# Adafruit_SHT31-D_STEMMA_QT_Breakout.net
KiCad netlist of a schematic drawn in EAGLE
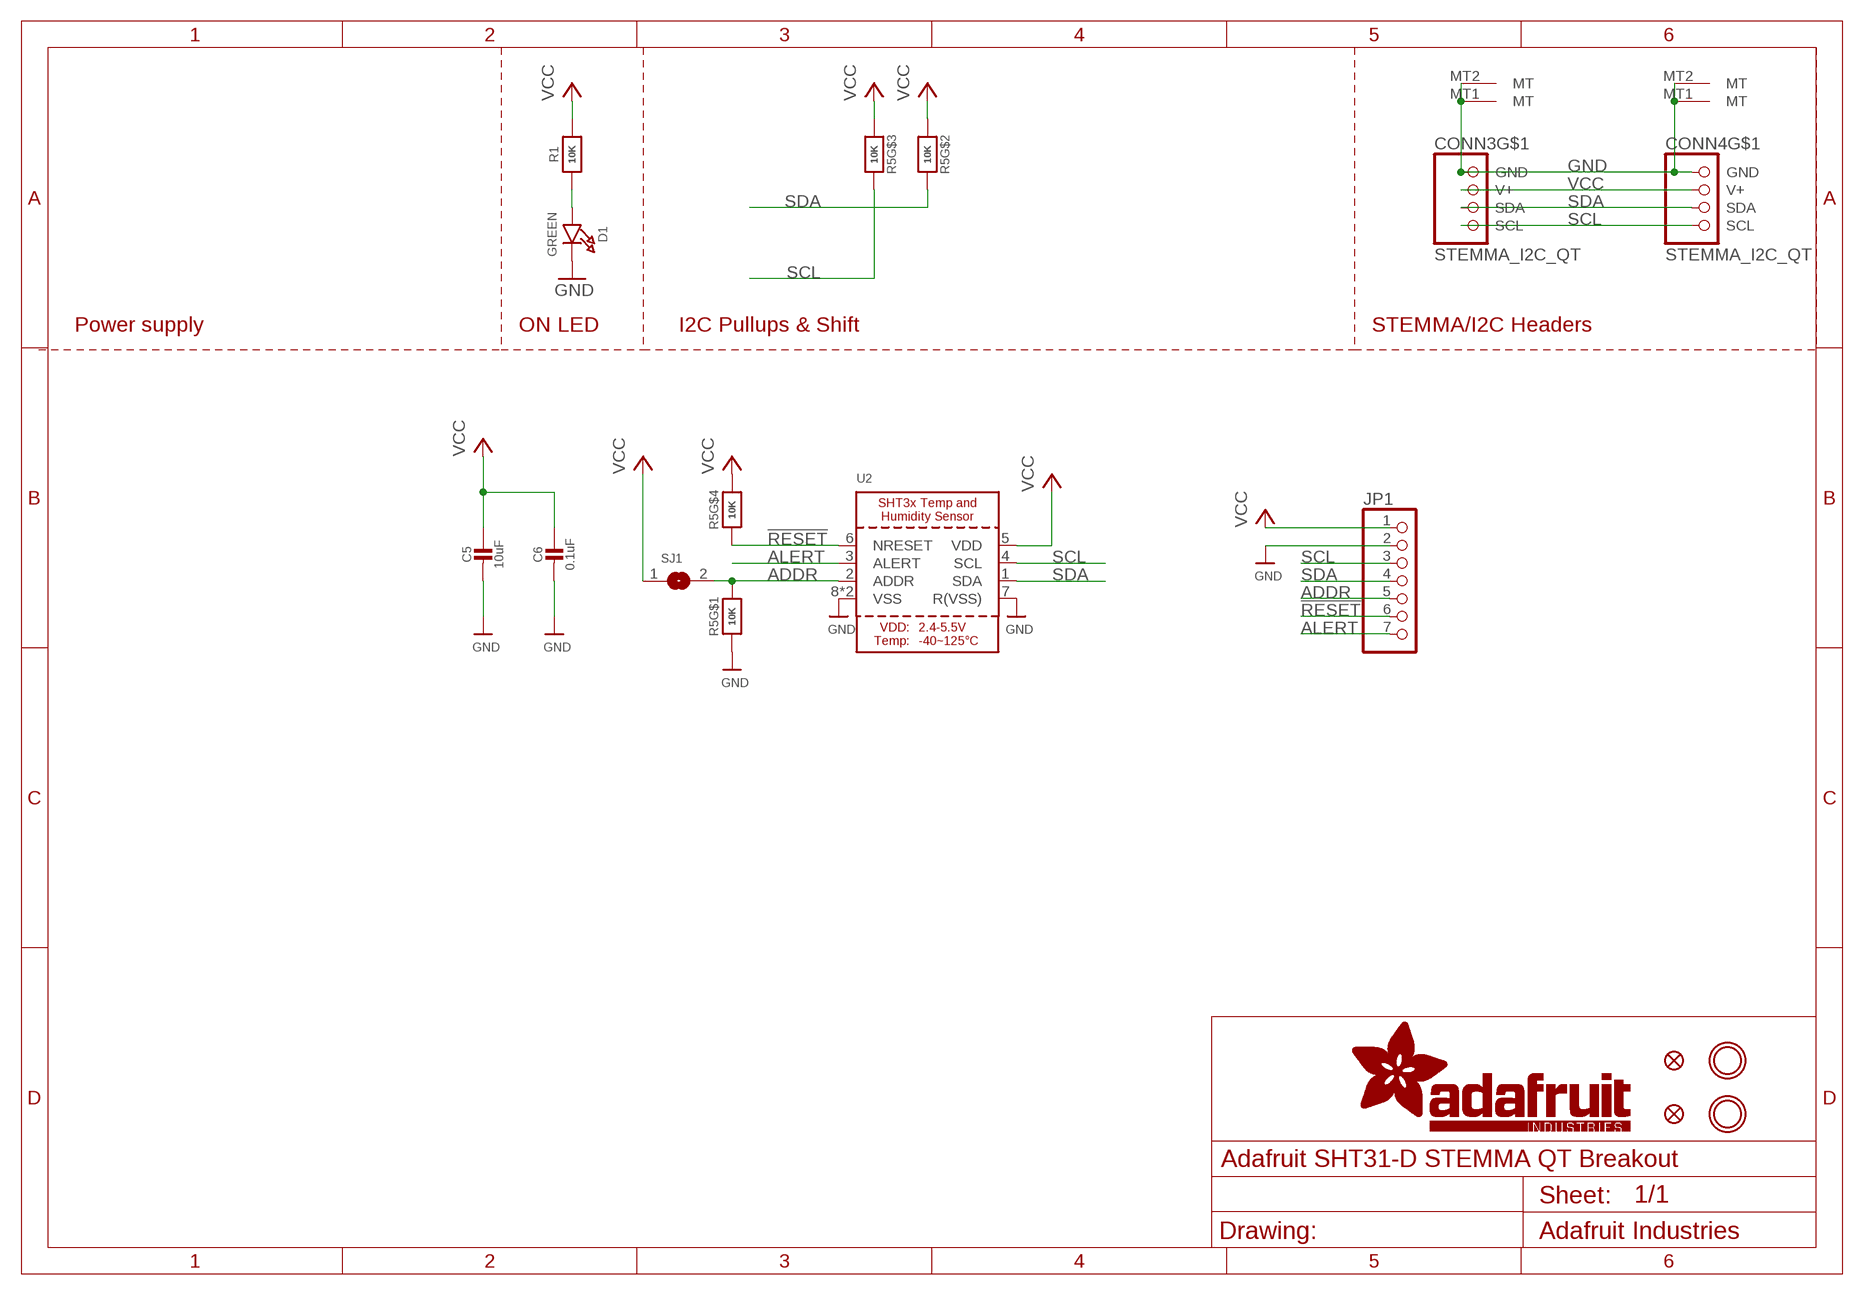
[diagram p0: schematic, sheet 1]

(export (version "E")
  (design (tool "Eeschema 10.0.6"))
  (components
    (comp (ref "C5")
      (value "10uF")
      (footprint "eagle-import:0805-NO")
      (libsource (lib "eagle-import") (part "CAP_CERAMIC0805-NOOUTLINE"))
    )
    (comp (ref "C6")
      (value "0.1uF")
      (footprint "eagle-import:0603-NO")
      (libsource (lib "eagle-import") (part "CAP_CERAMIC0603_NO"))
    )
    (comp (ref "CONN3")
      (value "STEMMA_I2C_QT")
      (footprint "eagle-import:JST_SH4")
      (libsource (lib "eagle-import") (part "STEMMA_I2C_QT"))
    )
    (comp (ref "CONN4")
      (value "STEMMA_I2C_QT")
      (footprint "eagle-import:JST_SH4")
      (libsource (lib "eagle-import") (part "STEMMA_I2C_QT"))
    )
    (comp (ref "D1")
      (value "GREEN")
      (footprint "eagle-import:CHIPLED_0603_NOOUTLINE")
      (libsource (lib "eagle-import") (part "LED0603_NOOUTLINE"))
    )
    (comp (ref "FID3")
      (value "FIDUCIAL_1MM")
      (footprint "eagle-import:FIDUCIAL_1MM")
      (libsource (lib "eagle-import") (part "FIDUCIAL_1MM"))
    )
    (comp (ref "FID4")
      (value "FIDUCIAL_1MM")
      (footprint "eagle-import:FIDUCIAL_1MM")
      (libsource (lib "eagle-import") (part "FIDUCIAL_1MM"))
    )
    (comp (ref "JP1")
      (value "HEADER-1X770MIL")
      (footprint "eagle-import:1X07_ROUND_70")
      (libsource (lib "eagle-import") (part "HEADER-1X770MIL"))
    )
    (comp (ref "R1")
      (value "10K")
      (footprint "eagle-import:0603-NO")
      (libsource (lib "eagle-import") (part "RESISTOR_0603_NOOUT"))
    )
    (comp (ref "R5")
      (value "10K")
      (footprint "eagle-import:RESPACK_4X0603")
      (libsource (lib "eagle-import") (part "RESISTOR_4PACK"))
    )
    (comp (ref "SJ1")
      (value "SOLDERJUMPER")
      (footprint "eagle-import:SOLDERJUMPER_ARROW_NOPASTE")
      (libsource (lib "eagle-import") (part "SOLDERJUMPER"))
    )
    (comp (ref "U$19")
      (value "MOUNTINGHOLE2.5")
      (footprint "eagle-import:MOUNTINGHOLE_2.5_PLATED")
      (libsource (lib "eagle-import") (part "MOUNTINGHOLE2.5"))
    )
    (comp (ref "U$20")
      (value "MOUNTINGHOLE2.5")
      (footprint "eagle-import:MOUNTINGHOLE_2.5_PLATED")
      (libsource (lib "eagle-import") (part "MOUNTINGHOLE2.5"))
    )
    (comp (ref "U2")
      (value "SHT3X")
      (footprint "eagle-import:SHT3X")
      (libsource (lib "eagle-import") (part "SHT3X"))
    )
  )
  (nets
    (net (code "1") (name "/ADDR") (class "Default")
      (node (ref "JP1") (pin "5") (pinfunction "5_5") (pintype "passive"))
      (node (ref "R5") (pin "8") (pinfunction "2_8") (pintype "passive"))
      (node (ref "SJ1") (pin "2") (pinfunction "2_2") (pintype "passive"))
      (node (ref "U2") (pin "2") (pinfunction "ADDR_2") (pintype "bidirectional"))
    )
    (net (code "2") (name "/ALERT") (class "Default")
      (node (ref "JP1") (pin "7") (pinfunction "7_7") (pintype "passive"))
      (node (ref "U2") (pin "3") (pinfunction "ALERT_3") (pintype "bidirectional"))
    )
    (net (code "3") (name "/SCL") (class "Default")
      (node (ref "CONN3") (pin "4") (pinfunction "SCL_4") (pintype "passive"))
      (node (ref "CONN4") (pin "4") (pinfunction "SCL_4") (pintype "passive"))
      (node (ref "JP1") (pin "3") (pinfunction "3_3") (pintype "passive"))
      (node (ref "R5") (pin "6") (pinfunction "2_6") (pintype "passive"))
      (node (ref "U2") (pin "4") (pinfunction "SCL_4") (pintype "bidirectional"))
    )
    (net (code "4") (name "/SDA") (class "Default")
      (node (ref "CONN3") (pin "3") (pinfunction "SDA_3") (pintype "passive"))
      (node (ref "CONN4") (pin "3") (pinfunction "SDA_3") (pintype "passive"))
      (node (ref "JP1") (pin "4") (pinfunction "4_4") (pintype "passive"))
      (node (ref "R5") (pin "7") (pinfunction "2_7") (pintype "passive"))
      (node (ref "U2") (pin "1") (pinfunction "SDA_1") (pintype "bidirectional"))
    )
    (net (code "5") (name "/~{RESET}") (class "Default")
      (node (ref "JP1") (pin "6") (pinfunction "6_6") (pintype "passive"))
      (node (ref "R5") (pin "4") (pinfunction "1_4") (pintype "passive"))
      (node (ref "U2") (pin "6") (pinfunction "NRESET_6") (pintype "bidirectional"))
    )
    (net (code "6") (name "GND") (class "Default")
      (node (ref "C5") (pin "2") (pinfunction "2_2") (pintype "passive"))
      (node (ref "C6") (pin "2") (pinfunction "2_2") (pintype "passive"))
      (node (ref "CONN3") (pin "1") (pinfunction "GND_1") (pintype "passive"))
      (node (ref "CONN3") (pin "MT1") (pinfunction "MT_MT1") (pintype "bidirectional"))
      (node (ref "CONN3") (pin "MT2") (pinfunction "MT_MT2") (pintype "bidirectional"))
      (node (ref "CONN4") (pin "1") (pinfunction "GND_1") (pintype "passive"))
      (node (ref "CONN4") (pin "MT1") (pinfunction "MT_MT1") (pintype "bidirectional"))
      (node (ref "CONN4") (pin "MT2") (pinfunction "MT_MT2") (pintype "bidirectional"))
      (node (ref "D1") (pin "C") (pinfunction "C_C") (pintype "passive"))
      (node (ref "JP1") (pin "2") (pinfunction "2_2") (pintype "passive"))
      (node (ref "R5") (pin "1") (pinfunction "1_1") (pintype "passive"))
      (node (ref "U2") (pin "7") (pinfunction "R(VSS)_7") (pintype "bidirectional"))
      (node (ref "U2") (pin "8") (pinfunction "VSS_8") (pintype "power_in"))
      (node (ref "U2") (pin "THERMAL") (pinfunction "VSS_THERMAL") (pintype "power_in"))
    )
    (net (code "7") (name "Net-(D1-PadA)") (class "Default")
      (node (ref "D1") (pin "A") (pinfunction "A_A") (pintype "passive"))
      (node (ref "R1") (pin "1") (pinfunction "1_1") (pintype "passive"))
    )
    (net (code "8") (name "VCC") (class "Default")
      (node (ref "C5") (pin "1") (pinfunction "1_1") (pintype "passive"))
      (node (ref "C6") (pin "1") (pinfunction "1_1") (pintype "passive"))
      (node (ref "CONN3") (pin "2") (pinfunction "V+_2") (pintype "passive"))
      (node (ref "CONN4") (pin "2") (pinfunction "V+_2") (pintype "passive"))
      (node (ref "JP1") (pin "1") (pinfunction "1_1") (pintype "passive"))
      (node (ref "R1") (pin "2") (pinfunction "2_2") (pintype "passive"))
      (node (ref "R5") (pin "2") (pinfunction "1_2") (pintype "passive"))
      (node (ref "R5") (pin "3") (pinfunction "1_3") (pintype "passive"))
      (node (ref "R5") (pin "5") (pinfunction "2_5") (pintype "passive"))
      (node (ref "SJ1") (pin "1") (pinfunction "1_1") (pintype "passive"))
      (node (ref "U2") (pin "5") (pinfunction "VDD_5") (pintype "power_in"))
    )
  )
)
